# 64K_SRAM_Memory.net
KiCad netlist of a schematic drawn in EAGLE
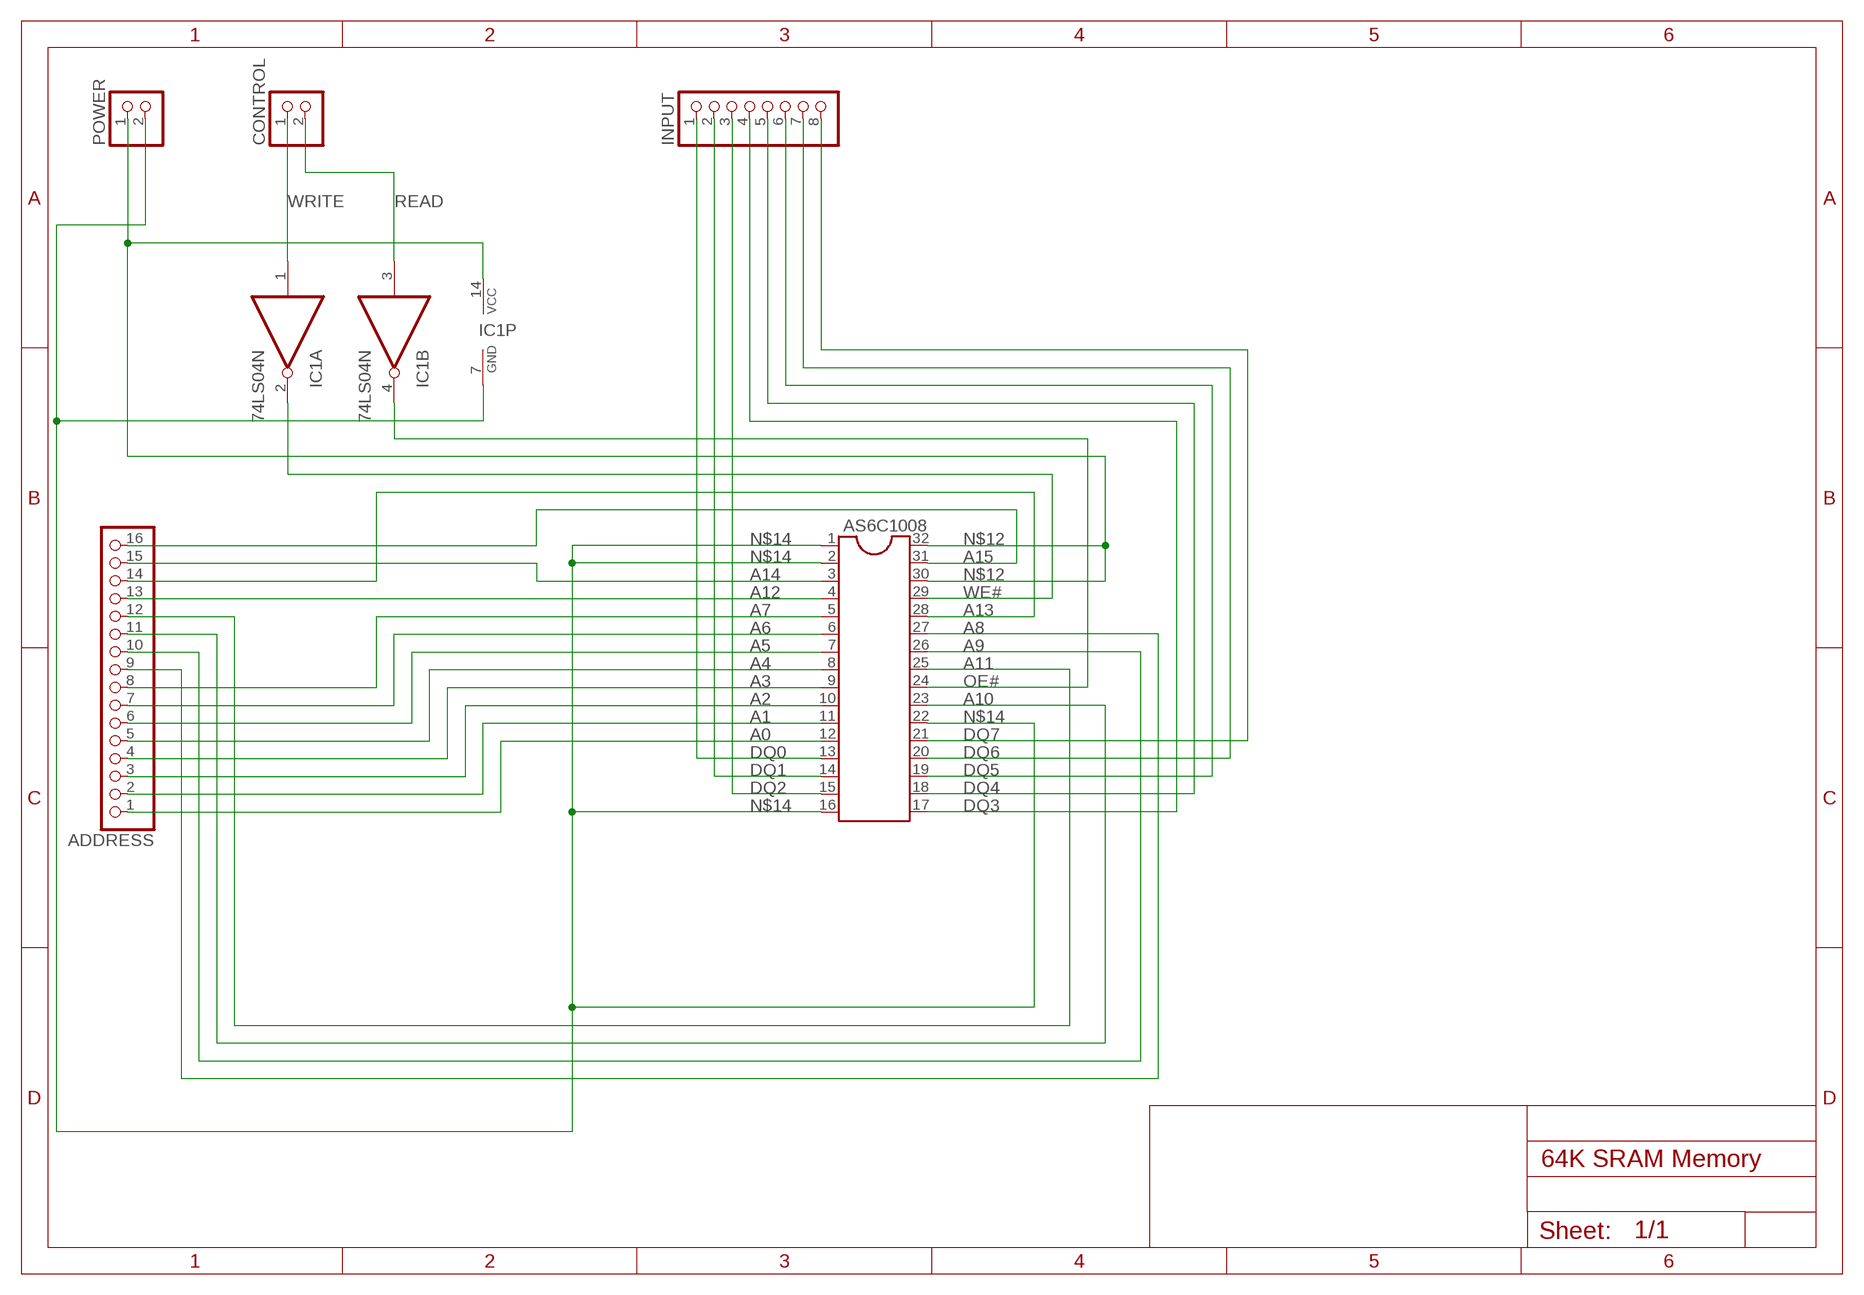
[diagram p0: schematic, sheet 1]

(export (version "E")
  (design (tool "Eeschema 10.0.6"))
  (components
    (comp (ref "ADDRESS")
      (value "PINHD-1X16")
      (footprint "eagle-import:1X16")
      (libsource (lib "eagle-import") (part "PINHD-1X16"))
    )
    (comp (ref "AS6C1008")
      (value "DIL32")
      (footprint "eagle-import:DIL32")
      (libsource (lib "eagle-import") (part "DIL32"))
    )
    (comp (ref "CONTROL")
      (value "PINHD-1X2")
      (footprint "eagle-import:1X02")
      (libsource (lib "eagle-import") (part "PINHD-1X2"))
    )
    (comp (ref "IC1")
      (value "74LS04N")
      (footprint "eagle-import:DIL14")
      (libsource (lib "eagle-import") (part "7404NLS"))
    )
    (comp (ref "INPUT")
      (value "PINHD-1X8")
      (footprint "eagle-import:1X08")
      (libsource (lib "eagle-import") (part "PINHD-1X8"))
    )
    (comp (ref "POWER")
      (value "PINHD-1X2")
      (footprint "eagle-import:1X02")
      (libsource (lib "eagle-import") (part "PINHD-1X2"))
    )
  )
  (nets
    (net (code "1") (name "/A0") (class "Default")
      (node (ref "ADDRESS") (pin "1") (pinfunction "1_1") (pintype "passive"))
      (node (ref "AS6C1008") (pin "12") (pinfunction "12_12") (pintype "passive"))
    )
    (net (code "2") (name "/A1") (class "Default")
      (node (ref "ADDRESS") (pin "2") (pinfunction "2_2") (pintype "passive"))
      (node (ref "AS6C1008") (pin "11") (pinfunction "11_11") (pintype "passive"))
    )
    (net (code "3") (name "/A2") (class "Default")
      (node (ref "ADDRESS") (pin "3") (pinfunction "3_3") (pintype "passive"))
      (node (ref "AS6C1008") (pin "10") (pinfunction "10_10") (pintype "passive"))
    )
    (net (code "4") (name "/A3") (class "Default")
      (node (ref "ADDRESS") (pin "4") (pinfunction "4_4") (pintype "passive"))
      (node (ref "AS6C1008") (pin "9") (pinfunction "9_9") (pintype "passive"))
    )
    (net (code "5") (name "/A4") (class "Default")
      (node (ref "ADDRESS") (pin "5") (pinfunction "5_5") (pintype "passive"))
      (node (ref "AS6C1008") (pin "8") (pinfunction "8_8") (pintype "passive"))
    )
    (net (code "6") (name "/A5") (class "Default")
      (node (ref "ADDRESS") (pin "6") (pinfunction "6_6") (pintype "passive"))
      (node (ref "AS6C1008") (pin "7") (pinfunction "7_7") (pintype "passive"))
    )
    (net (code "7") (name "/A6") (class "Default")
      (node (ref "ADDRESS") (pin "7") (pinfunction "7_7") (pintype "passive"))
      (node (ref "AS6C1008") (pin "6") (pinfunction "6_6") (pintype "passive"))
    )
    (net (code "8") (name "/A7") (class "Default")
      (node (ref "ADDRESS") (pin "8") (pinfunction "8_8") (pintype "passive"))
      (node (ref "AS6C1008") (pin "5") (pinfunction "5_5") (pintype "passive"))
    )
    (net (code "9") (name "/A8") (class "Default")
      (node (ref "ADDRESS") (pin "9") (pinfunction "9_9") (pintype "passive"))
      (node (ref "AS6C1008") (pin "27") (pinfunction "27_27") (pintype "passive"))
    )
    (net (code "10") (name "/A9") (class "Default")
      (node (ref "ADDRESS") (pin "10") (pinfunction "10_10") (pintype "passive"))
      (node (ref "AS6C1008") (pin "26") (pinfunction "26_26") (pintype "passive"))
    )
    (net (code "11") (name "/A10") (class "Default")
      (node (ref "ADDRESS") (pin "11") (pinfunction "11_11") (pintype "passive"))
      (node (ref "AS6C1008") (pin "23") (pinfunction "23_23") (pintype "passive"))
    )
    (net (code "12") (name "/A11") (class "Default")
      (node (ref "ADDRESS") (pin "12") (pinfunction "12_12") (pintype "passive"))
      (node (ref "AS6C1008") (pin "25") (pinfunction "25_25") (pintype "passive"))
    )
    (net (code "13") (name "/A12") (class "Default")
      (node (ref "ADDRESS") (pin "13") (pinfunction "13_13") (pintype "passive"))
      (node (ref "AS6C1008") (pin "4") (pinfunction "4_4") (pintype "passive"))
    )
    (net (code "14") (name "/A13") (class "Default")
      (node (ref "ADDRESS") (pin "14") (pinfunction "14_14") (pintype "passive"))
      (node (ref "AS6C1008") (pin "28") (pinfunction "28_28") (pintype "passive"))
    )
    (net (code "15") (name "/A14") (class "Default")
      (node (ref "ADDRESS") (pin "15") (pinfunction "15_15") (pintype "passive"))
      (node (ref "AS6C1008") (pin "3") (pinfunction "3_3") (pintype "passive"))
    )
    (net (code "16") (name "/A15") (class "Default")
      (node (ref "ADDRESS") (pin "16") (pinfunction "16_16") (pintype "passive"))
      (node (ref "AS6C1008") (pin "31") (pinfunction "31_31") (pintype "passive"))
    )
    (net (code "17") (name "/DQ0") (class "Default")
      (node (ref "AS6C1008") (pin "13") (pinfunction "13_13") (pintype "passive"))
      (node (ref "INPUT") (pin "1") (pinfunction "1_1") (pintype "passive"))
    )
    (net (code "18") (name "/DQ1") (class "Default")
      (node (ref "AS6C1008") (pin "14") (pinfunction "14_14") (pintype "passive"))
      (node (ref "INPUT") (pin "2") (pinfunction "2_2") (pintype "passive"))
    )
    (net (code "19") (name "/DQ2") (class "Default")
      (node (ref "AS6C1008") (pin "15") (pinfunction "15_15") (pintype "passive"))
      (node (ref "INPUT") (pin "3") (pinfunction "3_3") (pintype "passive"))
    )
    (net (code "20") (name "/DQ3") (class "Default")
      (node (ref "AS6C1008") (pin "17") (pinfunction "17_17") (pintype "passive"))
      (node (ref "INPUT") (pin "4") (pinfunction "4_4") (pintype "passive"))
    )
    (net (code "21") (name "/DQ4") (class "Default")
      (node (ref "AS6C1008") (pin "18") (pinfunction "18_18") (pintype "passive"))
      (node (ref "INPUT") (pin "5") (pinfunction "5_5") (pintype "passive"))
    )
    (net (code "22") (name "/DQ5") (class "Default")
      (node (ref "AS6C1008") (pin "19") (pinfunction "19_19") (pintype "passive"))
      (node (ref "INPUT") (pin "6") (pinfunction "6_6") (pintype "passive"))
    )
    (net (code "23") (name "/DQ6") (class "Default")
      (node (ref "AS6C1008") (pin "20") (pinfunction "20_20") (pintype "passive"))
      (node (ref "INPUT") (pin "7") (pinfunction "7_7") (pintype "passive"))
    )
    (net (code "24") (name "/DQ7") (class "Default")
      (node (ref "AS6C1008") (pin "21") (pinfunction "21_21") (pintype "passive"))
      (node (ref "INPUT") (pin "8") (pinfunction "8_8") (pintype "passive"))
    )
    (net (code "25") (name "/N$12") (class "Default")
      (node (ref "AS6C1008") (pin "30") (pinfunction "30_30") (pintype "passive"))
      (node (ref "AS6C1008") (pin "32") (pinfunction "32_32") (pintype "passive"))
      (node (ref "IC1") (pin "14") (pinfunction "VCC_14") (pintype "power_in"))
      (node (ref "POWER") (pin "1") (pinfunction "1_1") (pintype "passive"))
    )
    (net (code "26") (name "/N$14") (class "Default")
      (node (ref "AS6C1008") (pin "1") (pinfunction "1_1") (pintype "passive"))
      (node (ref "AS6C1008") (pin "16") (pinfunction "16_16") (pintype "passive"))
      (node (ref "AS6C1008") (pin "2") (pinfunction "2_2") (pintype "passive"))
      (node (ref "AS6C1008") (pin "22") (pinfunction "22_22") (pintype "passive"))
      (node (ref "IC1") (pin "7") (pinfunction "GND_7") (pintype "power_in"))
      (node (ref "POWER") (pin "2") (pinfunction "2_2") (pintype "passive"))
    )
    (net (code "27") (name "/OE#") (class "Default")
      (node (ref "AS6C1008") (pin "24") (pinfunction "24_24") (pintype "passive"))
      (node (ref "IC1") (pin "4") (pinfunction "O_4") (pintype "output"))
    )
    (net (code "28") (name "/READ") (class "Default")
      (node (ref "CONTROL") (pin "2") (pinfunction "2_2") (pintype "passive"))
      (node (ref "IC1") (pin "3") (pinfunction "I_3") (pintype "input"))
    )
    (net (code "29") (name "/WE#") (class "Default")
      (node (ref "AS6C1008") (pin "29") (pinfunction "29_29") (pintype "passive"))
      (node (ref "IC1") (pin "2") (pinfunction "O_2") (pintype "output"))
    )
    (net (code "30") (name "/WRITE") (class "Default")
      (node (ref "CONTROL") (pin "1") (pinfunction "1_1") (pintype "passive"))
      (node (ref "IC1") (pin "1") (pinfunction "I_1") (pintype "input"))
    )
  )
)
